# Endstop_Channel.net
KiCad netlist of a schematic drawn in Altium Designer
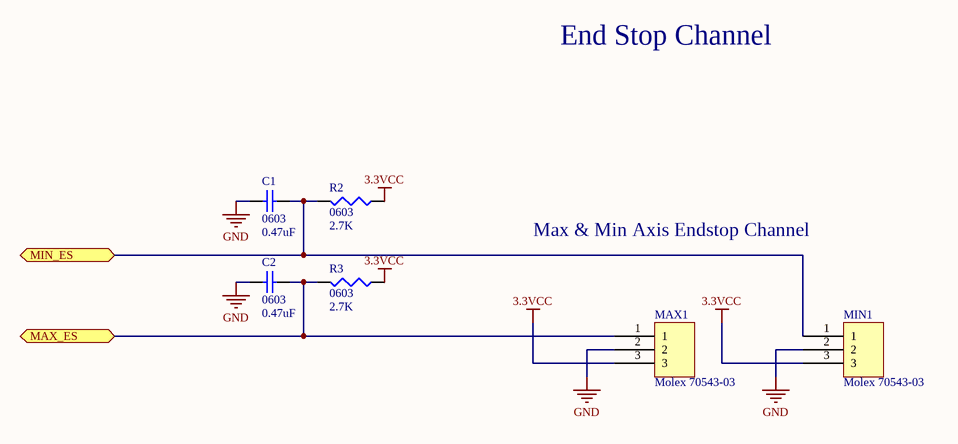
[diagram p0: Endstop Channel.SchDoc]

(export (version "E")
  (design (tool "Eeschema 10.0.6"))
  (components
    (comp (ref "C1")
      (value "0603")
      (footprint "1608[0603]")
      (description "Capacitor (Semiconductor SIM Model)")
      (fields (field (name "ALTIUM_VALUE") "0.47uF") (field (name "PUBLISHER") "Altium Limited"))
      (libsource (lib "Miscellaneous Devices") (part "Cap Semi"))
    )
    (comp (ref "C2")
      (value "0603")
      (footprint "1608[0603]")
      (description "Capacitor (Semiconductor SIM Model)")
      (fields (field (name "ALTIUM_VALUE") "0.47uF") (field (name "PUBLISHER") "Altium Limited"))
      (libsource (lib "Miscellaneous Devices") (part "Cap Semi"))
    )
    (comp (ref "MAX1")
      (value "Molex 70543-03")
      (footprint "70543-03")
      (libsource (lib "RADMBo Schematic Library") (part "Molex Endstop"))
    )
    (comp (ref "MIN1")
      (value "Molex 70543-03")
      (footprint "70543-03")
      (libsource (lib "RADMBo Schematic Library") (part "Molex Endstop"))
    )
    (comp (ref "R2")
      (value "0603")
      (footprint "J1-0603")
      (description "Resistor")
      (fields (field (name "ALTIUM_VALUE") "2.7K") (field (name "PUBLISHER") "Altium Limited"))
      (libsource (lib "Miscellaneous Devices") (part "Res3"))
    )
    (comp (ref "R3")
      (value "0603")
      (footprint "J1-0603")
      (description "Resistor")
      (fields (field (name "ALTIUM_VALUE") "2.7K") (field (name "PUBLISHER") "Altium Limited"))
      (libsource (lib "Miscellaneous Devices") (part "Res3"))
    )
  )
  (nets
    (net (code "1") (name "/MAX_ES") (class "Default")
      (node (ref "C2") (pin "1") (pinfunction "1_1") (pintype "passive"))
      (node (ref "MAX1") (pin "1") (pinfunction "1_1") (pintype "passive"))
      (node (ref "R3") (pin "2") (pinfunction "2_2") (pintype "passive"))
    )
    (net (code "2") (name "/MIN_ES") (class "Default")
      (node (ref "C1") (pin "1") (pinfunction "1_1") (pintype "passive"))
      (node (ref "MIN1") (pin "1") (pinfunction "1_1") (pintype "passive"))
      (node (ref "R2") (pin "2") (pinfunction "2_2") (pintype "passive"))
    )
    (net (code "3") (name "3.3VCC") (class "Default")
      (node (ref "MAX1") (pin "3") (pinfunction "3_3") (pintype "passive"))
      (node (ref "MIN1") (pin "3") (pinfunction "3_3") (pintype "passive"))
      (node (ref "R2") (pin "1") (pinfunction "1_1") (pintype "passive"))
      (node (ref "R3") (pin "1") (pinfunction "1_1") (pintype "passive"))
    )
    (net (code "4") (name "GND") (class "Default")
      (node (ref "C1") (pin "2") (pinfunction "2_2") (pintype "passive"))
      (node (ref "C2") (pin "2") (pinfunction "2_2") (pintype "passive"))
      (node (ref "MAX1") (pin "2") (pinfunction "2_2") (pintype "passive"))
      (node (ref "MIN1") (pin "2") (pinfunction "2_2") (pintype "passive"))
    )
  )
)
